# clvHd.net
KiCad netlist of a schematic drawn in EAGLE
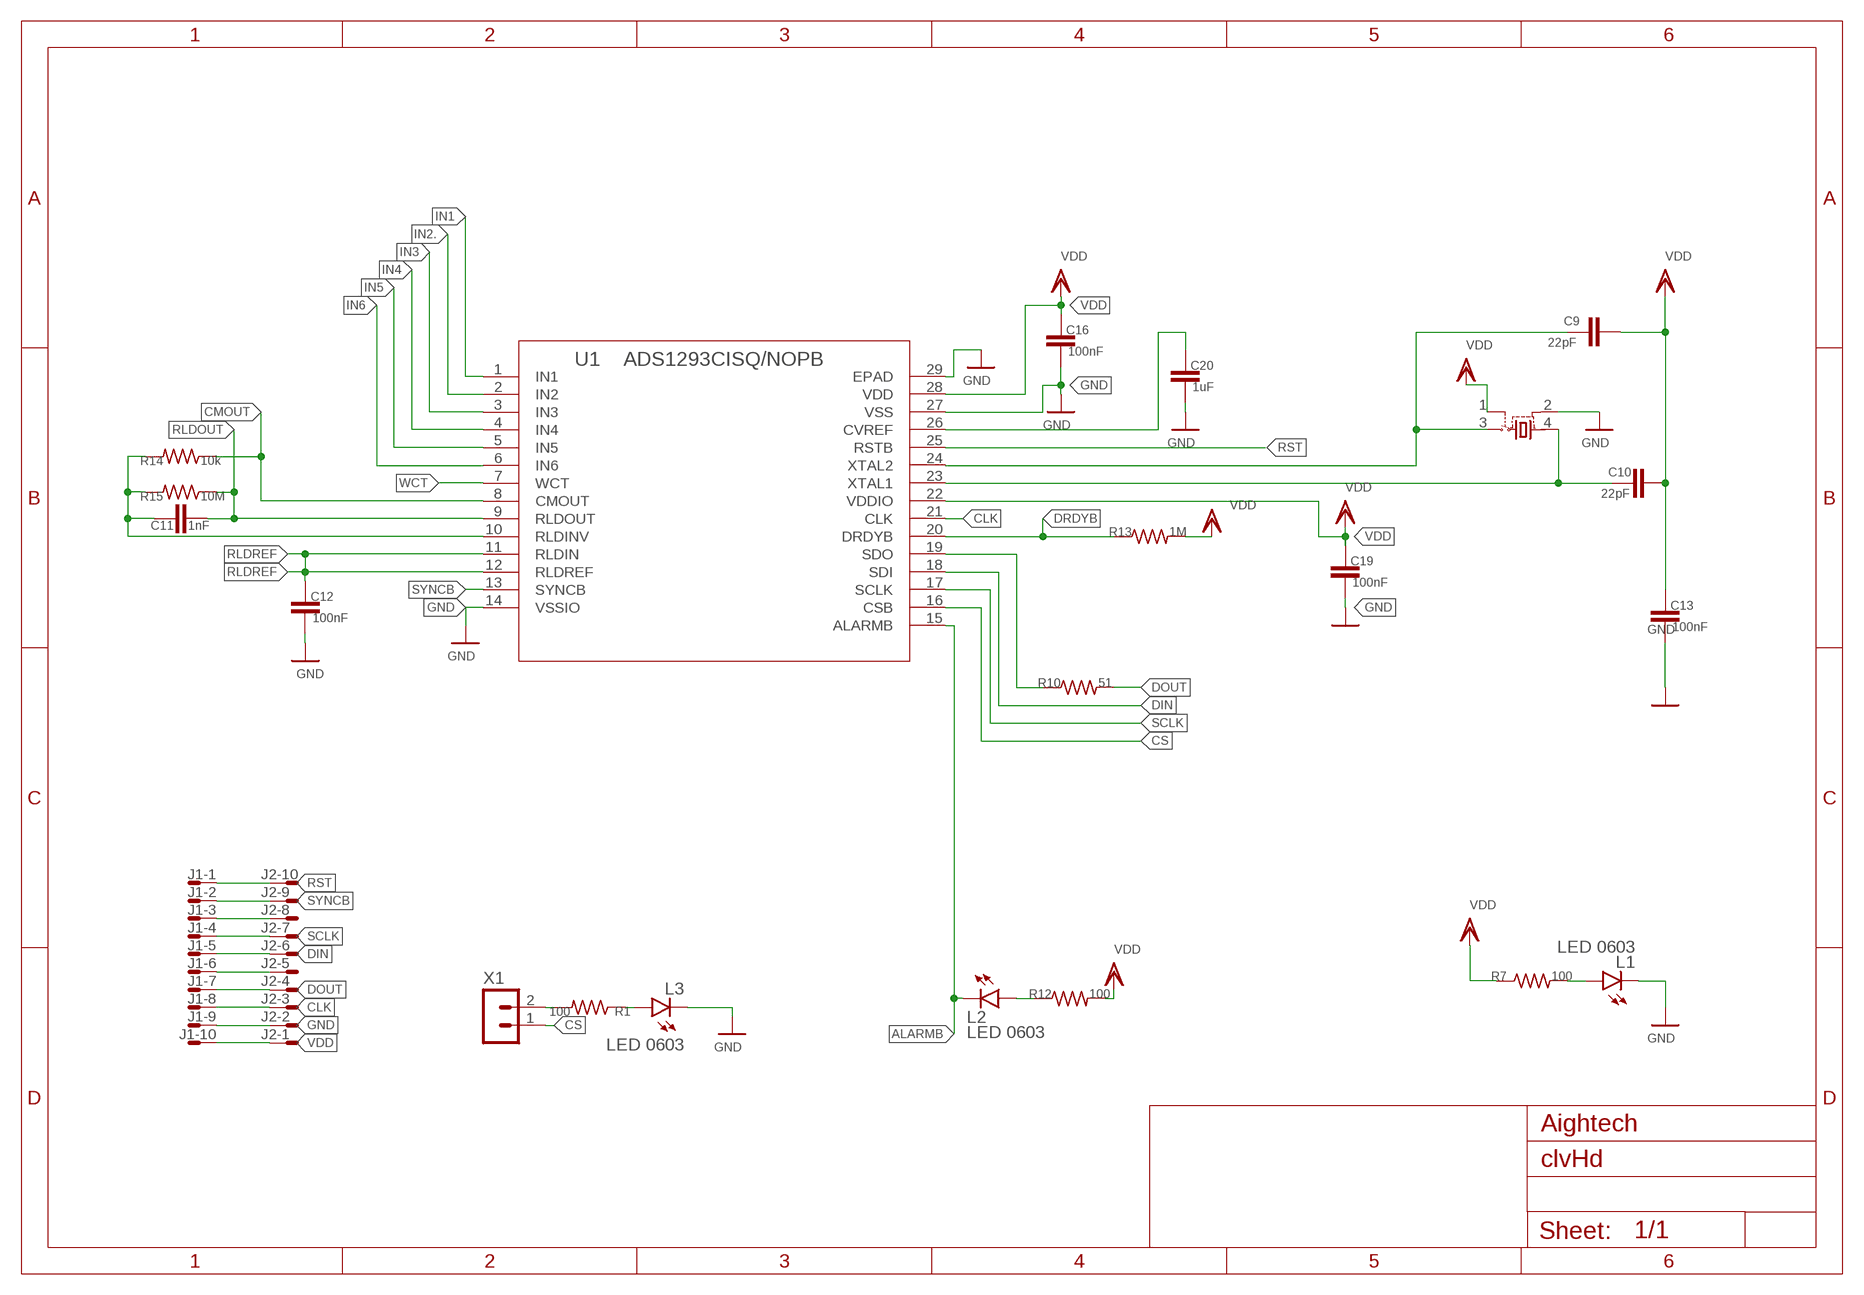
[diagram p0: schematic, sheet 1]

(export (version "E")
  (design (tool "Eeschema 10.0.6"))
  (components
    (comp (ref "C9")
      (value "22pF")
      (footprint "eagle-import:C0402")
      (libsource (lib "eagle-import") (part "C-EUC0402"))
    )
    (comp (ref "C10")
      (value "22pF")
      (footprint "eagle-import:C0402")
      (libsource (lib "eagle-import") (part "C-EUC0402"))
    )
    (comp (ref "C11")
      (value "1nF")
      (footprint "eagle-import:C0402")
      (libsource (lib "eagle-import") (part "C-EUC0402"))
    )
    (comp (ref "C12")
      (value "100nF")
      (footprint "eagle-import:C0402")
      (libsource (lib "eagle-import") (part "C-EUC0402"))
    )
    (comp (ref "C13")
      (value "100nF")
      (footprint "eagle-import:C0402")
      (libsource (lib "eagle-import") (part "C-EUC0402"))
    )
    (comp (ref "C16")
      (value "100nF")
      (footprint "eagle-import:C0402")
      (libsource (lib "eagle-import") (part "C-EUC0402"))
    )
    (comp (ref "C19")
      (value "100nF")
      (footprint "eagle-import:C0402")
      (libsource (lib "eagle-import") (part "C-EUC0402"))
    )
    (comp (ref "C20")
      (value "1uF")
      (footprint "eagle-import:C0402")
      (libsource (lib "eagle-import") (part "C-EUC0402"))
    )
    (comp (ref "J1")
      (value "XF2J-1024-12")
      (footprint "eagle-import:XF2J-1024-12")
      (libsource (lib "eagle-import") (part "XF2-10?24-12J"))
    )
    (comp (ref "J2")
      (value "XF2J-1024-12")
      (footprint "eagle-import:XF2J-1024-12")
      (libsource (lib "eagle-import") (part "XF2-10?24-12J"))
    )
    (comp (ref "L1")
      (value "LED 0603")
      (footprint "eagle-import:CHIP-LED0603")
      (libsource (lib "eagle-import") (part "LEDCHIP-LED0603"))
    )
    (comp (ref "L2")
      (value "LED 0603")
      (footprint "eagle-import:CHIP-LED0603")
      (libsource (lib "eagle-import") (part "LEDCHIP-LED0603"))
    )
    (comp (ref "L3")
      (value "LED 0603")
      (footprint "eagle-import:CHIP-LED0603")
      (libsource (lib "eagle-import") (part "LEDCHIP-LED0603"))
    )
    (comp (ref "R1")
      (value "100")
      (footprint "eagle-import:R0402")
      (libsource (lib "eagle-import") (part "rcl_334_R-US_R0402"))
    )
    (comp (ref "R7")
      (value "100")
      (footprint "eagle-import:R0402")
      (libsource (lib "eagle-import") (part "rcl_334_R-US_R0402"))
    )
    (comp (ref "R10")
      (value "51")
      (footprint "eagle-import:R0402")
      (libsource (lib "eagle-import") (part "rcl_334_R-US_R0402"))
    )
    (comp (ref "R12")
      (value "100")
      (footprint "eagle-import:R0402")
      (libsource (lib "eagle-import") (part "rcl_334_R-US_R0402"))
    )
    (comp (ref "R13")
      (value "1M")
      (footprint "eagle-import:R0402")
      (libsource (lib "eagle-import") (part "R-US_R0402"))
    )
    (comp (ref "R14")
      (value "10k")
      (footprint "eagle-import:R0402")
      (libsource (lib "eagle-import") (part "rcl_334_R-US_R0402"))
    )
    (comp (ref "R15")
      (value "10M")
      (footprint "eagle-import:R0402")
      (libsource (lib "eagle-import") (part "rcl_334_R-US_R0402"))
    )
    (comp (ref "U$1")
      (value "C387328")
      (footprint "eagle-import:SMD-3225_4P")
      (libsource (lib "eagle-import") (part "C387328"))
    )
    (comp (ref "U1")
      (value "ADS1293CISQ/NOPB")
      (footprint "eagle-import:RSG28_3P6X3P6_TEX")
      (libsource (lib "eagle-import") (part "ADS1293CISQ/NOPB"))
    )
    (comp (ref "X1")
      (value "BM02B-SRSS-TB")
      (footprint "eagle-import:BM02B-SRSS-TB")
      (libsource (lib "eagle-import") (part "BM02B-SRSS-TB"))
    )
  )
  (nets
    (net (code "1") (name "ALARMB") (class "Default")
      (node (ref "L2") (pin "C") (pinfunction "C_C") (pintype "passive"))
      (node (ref "U1") (pin "15") (pinfunction "ALARMB_15") (pintype "output"))
    )
    (net (code "2") (name "CLK") (class "Default")
      (node (ref "J1") (pin "8") (pinfunction "MS_8") (pintype "passive"))
      (node (ref "J2") (pin "3") (pinfunction "MS_3") (pintype "passive"))
      (node (ref "U1") (pin "21") (pinfunction "CLK_21") (pintype "bidirectional"))
    )
    (net (code "3") (name "CMOUT") (class "Default")
      (node (ref "R14") (pin "1") (pinfunction "1_1") (pintype "passive"))
      (node (ref "U1") (pin "8") (pinfunction "CMOUT_8") (pintype "output"))
    )
    (net (code "4") (name "CS") (class "Default")
      (node (ref "U1") (pin "16") (pinfunction "CSB_16") (pintype "input"))
      (node (ref "X1") (pin "1") (pinfunction "1_1") (pintype "passive"))
    )
    (net (code "5") (name "DIN") (class "Default")
      (node (ref "J1") (pin "5") (pinfunction "MS_5") (pintype "passive"))
      (node (ref "J2") (pin "6") (pinfunction "MS_6") (pintype "passive"))
      (node (ref "U1") (pin "18") (pinfunction "SDI_18") (pintype "input"))
    )
    (net (code "6") (name "DOUT") (class "Default")
      (node (ref "J1") (pin "7") (pinfunction "MS_7") (pintype "passive"))
      (node (ref "J2") (pin "4") (pinfunction "MS_4") (pintype "passive"))
      (node (ref "R10") (pin "2") (pinfunction "2_2") (pintype "passive"))
    )
    (net (code "7") (name "DRDYB") (class "Default")
      (node (ref "R13") (pin "1") (pinfunction "1_1") (pintype "passive"))
      (node (ref "U1") (pin "20") (pinfunction "DRDYB_20") (pintype "output"))
    )
    (net (code "8") (name "GND") (class "Default")
      (node (ref "C12") (pin "2") (pinfunction "2_2") (pintype "passive"))
      (node (ref "C13") (pin "2") (pinfunction "2_2") (pintype "passive"))
      (node (ref "C16") (pin "2") (pinfunction "2_2") (pintype "passive"))
      (node (ref "C19") (pin "2") (pinfunction "2_2") (pintype "passive"))
      (node (ref "C20") (pin "2") (pinfunction "2_2") (pintype "passive"))
      (node (ref "J1") (pin "3") (pinfunction "MS_3") (pintype "passive"))
      (node (ref "J1") (pin "6") (pinfunction "MS_6") (pintype "passive"))
      (node (ref "J1") (pin "9") (pinfunction "MS_9") (pintype "passive"))
      (node (ref "J2") (pin "2") (pinfunction "MS_2") (pintype "passive"))
      (node (ref "J2") (pin "5") (pinfunction "MS_5") (pintype "passive"))
      (node (ref "J2") (pin "8") (pinfunction "MS_8") (pintype "passive"))
      (node (ref "L1") (pin "C") (pinfunction "C_C") (pintype "passive"))
      (node (ref "L3") (pin "C") (pinfunction "C_C") (pintype "passive"))
      (node (ref "U$1") (pin "2") (pinfunction "GND_2") (pintype "power_in"))
      (node (ref "U1") (pin "14") (pinfunction "VSSIO_14") (pintype "power_in"))
      (node (ref "U1") (pin "27") (pinfunction "VSS_27") (pintype "power_in"))
      (node (ref "U1") (pin "29") (pinfunction "EPAD_29") (pintype "passive"))
    )
    (net (code "9") (name "IN1") (class "Default")
      (node (ref "U1") (pin "1") (pinfunction "IN1_1") (pintype "input"))
    )
    (net (code "10") (name "IN2.") (class "Default")
      (node (ref "U1") (pin "2") (pinfunction "IN2_2") (pintype "input"))
    )
    (net (code "11") (name "IN3") (class "Default")
      (node (ref "U1") (pin "3") (pinfunction "IN3_3") (pintype "input"))
    )
    (net (code "12") (name "IN4") (class "Default")
      (node (ref "U1") (pin "4") (pinfunction "IN4_4") (pintype "input"))
    )
    (net (code "13") (name "IN5") (class "Default")
      (node (ref "U1") (pin "5") (pinfunction "IN5_5") (pintype "input"))
    )
    (net (code "14") (name "IN6") (class "Default")
      (node (ref "U1") (pin "6") (pinfunction "IN6_6") (pintype "input"))
    )
    (net (code "15") (name "Net-(L1-PadA)") (class "Default")
      (node (ref "L1") (pin "A") (pinfunction "A_A") (pintype "passive"))
      (node (ref "R7") (pin "2") (pinfunction "2_2") (pintype "passive"))
    )
    (net (code "16") (name "Net-(L2-PadA)") (class "Default")
      (node (ref "L2") (pin "A") (pinfunction "A_A") (pintype "passive"))
      (node (ref "R12") (pin "1") (pinfunction "1_1") (pintype "passive"))
    )
    (net (code "17") (name "Net-(L3-PadA)") (class "Default")
      (node (ref "L3") (pin "A") (pinfunction "A_A") (pintype "passive"))
      (node (ref "R1") (pin "1") (pinfunction "1_1") (pintype "passive"))
    )
    (net (code "18") (name "Net-(R1-Pad2)") (class "Default")
      (node (ref "R1") (pin "2") (pinfunction "2_2") (pintype "passive"))
      (node (ref "X1") (pin "2") (pinfunction "2_2") (pintype "passive"))
    )
    (net (code "19") (name "Net-(U$1-OUT)") (class "Default")
      (node (ref "C9") (pin "2") (pinfunction "2_2") (pintype "passive"))
      (node (ref "U$1") (pin "3") (pinfunction "OUT_3") (pintype "output"))
      (node (ref "U1") (pin "24") (pinfunction "XTAL2_24") (pintype "input"))
    )
    (net (code "20") (name "Net-(U$1-VDD)") (class "Default")
      (node (ref "C10") (pin "2") (pinfunction "2_2") (pintype "passive"))
      (node (ref "U$1") (pin "4") (pinfunction "VDD_4") (pintype "power_in"))
      (node (ref "U1") (pin "23") (pinfunction "XTAL1_23") (pintype "input"))
    )
    (net (code "21") (name "Net-(U1-CVREF)") (class "Default")
      (node (ref "C20") (pin "1") (pinfunction "1_1") (pintype "passive"))
      (node (ref "U1") (pin "26") (pinfunction "CVREF_26") (pintype "bidirectional"))
    )
    (net (code "22") (name "Net-(U1-RLDINV)") (class "Default")
      (node (ref "C11") (pin "1") (pinfunction "1_1") (pintype "passive"))
      (node (ref "R14") (pin "2") (pinfunction "2_2") (pintype "passive"))
      (node (ref "R15") (pin "2") (pinfunction "2_2") (pintype "passive"))
      (node (ref "U1") (pin "10") (pinfunction "RLDINV_10") (pintype "input"))
    )
    (net (code "23") (name "Net-(U1-SDO)") (class "Default")
      (node (ref "R10") (pin "1") (pinfunction "1_1") (pintype "passive"))
      (node (ref "U1") (pin "19") (pinfunction "SDO_19") (pintype "output"))
    )
    (net (code "24") (name "RLDOUT") (class "Default")
      (node (ref "C11") (pin "2") (pinfunction "2_2") (pintype "passive"))
      (node (ref "R15") (pin "1") (pinfunction "1_1") (pintype "passive"))
      (node (ref "U1") (pin "9") (pinfunction "RLDOUT_9") (pintype "output"))
    )
    (net (code "25") (name "RLDREF") (class "Default")
      (node (ref "C12") (pin "1") (pinfunction "1_1") (pintype "passive"))
      (node (ref "U1") (pin "11") (pinfunction "RLDIN_11") (pintype "bidirectional"))
      (node (ref "U1") (pin "12") (pinfunction "RLDREF_12") (pintype "output"))
    )
    (net (code "26") (name "RST") (class "Default")
      (node (ref "J1") (pin "1") (pinfunction "MSV_1") (pintype "passive"))
      (node (ref "J2") (pin "10") (pinfunction "MS_10") (pintype "passive"))
      (node (ref "U1") (pin "25") (pinfunction "RSTB_25") (pintype "input"))
    )
    (net (code "27") (name "SCLK") (class "Default")
      (node (ref "J1") (pin "4") (pinfunction "MS_4") (pintype "passive"))
      (node (ref "J2") (pin "7") (pinfunction "MS_7") (pintype "passive"))
      (node (ref "U1") (pin "17") (pinfunction "SCLK_17") (pintype "input"))
    )
    (net (code "28") (name "SYNCB") (class "Default")
      (node (ref "J1") (pin "2") (pinfunction "MS_2") (pintype "passive"))
      (node (ref "J2") (pin "9") (pinfunction "MS_9") (pintype "passive"))
      (node (ref "U1") (pin "13") (pinfunction "SYNCB_13") (pintype "bidirectional"))
    )
    (net (code "29") (name "VDD") (class "Default")
      (node (ref "C10") (pin "1") (pinfunction "1_1") (pintype "passive"))
      (node (ref "C13") (pin "1") (pinfunction "1_1") (pintype "passive"))
      (node (ref "C16") (pin "1") (pinfunction "1_1") (pintype "passive"))
      (node (ref "C19") (pin "1") (pinfunction "1_1") (pintype "passive"))
      (node (ref "C9") (pin "1") (pinfunction "1_1") (pintype "passive"))
      (node (ref "J1") (pin "10") (pinfunction "MS_10") (pintype "passive"))
      (node (ref "J2") (pin "1") (pinfunction "MSV_1") (pintype "passive"))
      (node (ref "R12") (pin "2") (pinfunction "2_2") (pintype "passive"))
      (node (ref "R13") (pin "2") (pinfunction "2_2") (pintype "passive"))
      (node (ref "R7") (pin "1") (pinfunction "1_1") (pintype "passive"))
      (node (ref "U$1") (pin "1") (pinfunction "TRI_1") (pintype "input"))
      (node (ref "U1") (pin "22") (pinfunction "VDDIO_22") (pintype "power_in"))
      (node (ref "U1") (pin "28") (pinfunction "VDD_28") (pintype "power_in"))
    )
    (net (code "30") (name "WCT") (class "Default")
      (node (ref "U1") (pin "7") (pinfunction "WCT_7") (pintype "output"))
    )
  )
)
